# ALARM_POWER.net
KiCad netlist of a schematic drawn in Altium Designer
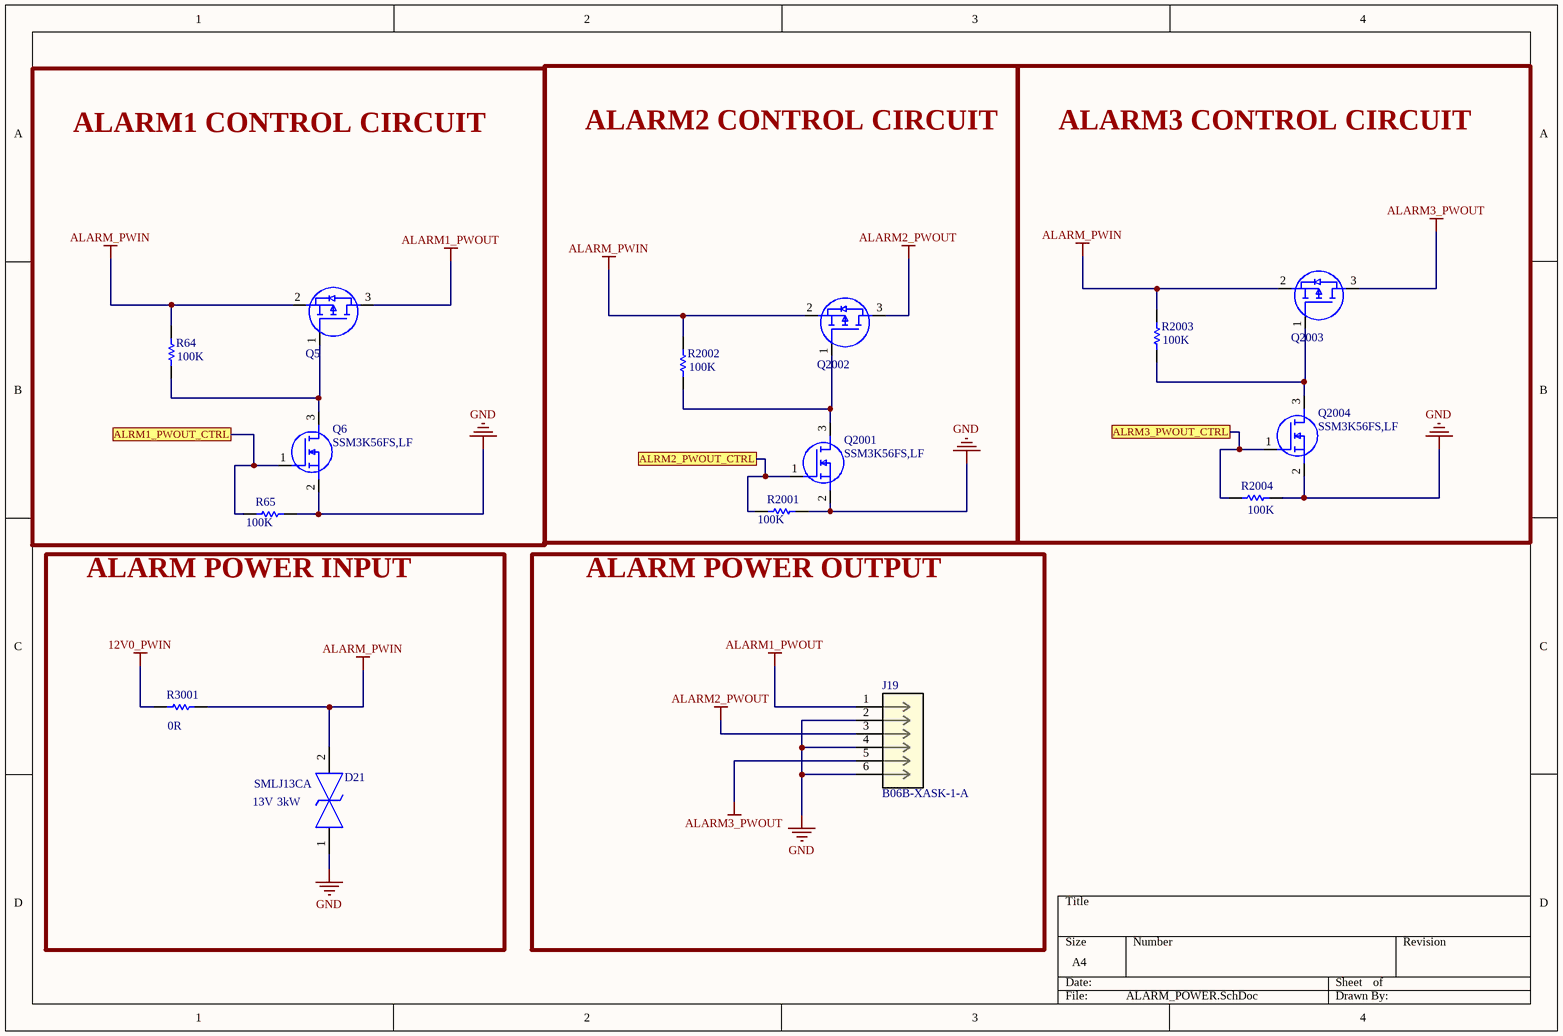
[diagram p0: ALARM_POWER.SchDoc]

(export (version "E")
  (design (tool "Eeschema 10.0.6"))
  (components
    (comp (ref "D21")
      (value "SMLJ13CA")
      (footprint "MareLux24Lib:DO-214AB, SMC")
      (description "21.5V Clamp 139.4A Ipp Tvs Diode Surface Mount SMC (DO-214AB)")
      (fields
        (field (name "ALTIUM_VALUE") "3kW")
        (field (name "TOLERANCE") "UD")
        (field (name "VOLTAGE") "13V")
      )
      (libsource (lib "MareLux24Lib") (part "SMLJ13CA"))
    )
    (comp (ref "J19")
      (value "B06B-XASK-1-A")
      (footprint "conn6_2132415-6_TEC")
      (description "No Description Available")
      (libsource (lib "2132415-6") (part "2132415-6"))
    )
    (comp (ref "Q5")
      (value "SQM110P06-8M9L_GE3")
      (footprint "SQM110P06_MOSFET")
      (description "P-Channel 60 V 110A (Tc) 230W (Tc) Surface Mount TO-263 (D2PAK)")
      (fields (field (name "VOLTAGE") "20 V") (field (name "POWER") "110A"))
      (libsource (lib "MareLux24Lib") (part "SQM110P06-8M9L_GE3"))
    )
    (comp (ref "Q6")
      (value "SSM3K56FS,LF")
      (footprint "SSM3K56FS,LF:SSM_TOS")
      (description "MOSFET (N-Channel)")
      (fields (field (name "MOUSER PART NUMBER") "757-SSM3K56FSLF"))
      (libsource (lib "*") (part "SSM3K56FS,LF"))
    )
    (comp (ref "Q2001")
      (value "SSM3K56FS,LF")
      (footprint "SSM3K56FS,LF:SSM_TOS")
      (description "MOSFET (N-Channel)")
      (fields (field (name "MOUSER PART NUMBER") "757-SSM3K56FSLF"))
      (libsource (lib "*") (part "SSM3K56FS,LF"))
    )
    (comp (ref "Q2002")
      (value "SQM110P06-8M9L_GE3")
      (footprint "SQM110P06_MOSFET")
      (description "P-Channel 60 V 110A (Tc) 230W (Tc) Surface Mount TO-263 (D2PAK)")
      (fields (field (name "VOLTAGE") "20 V") (field (name "POWER") "110A"))
      (libsource (lib "MareLux24Lib") (part "SQM110P06-8M9L_GE3"))
    )
    (comp (ref "Q2003")
      (value "SQM110P06-8M9L_GE3")
      (footprint "SQM110P06_MOSFET")
      (description "P-Channel 60 V 110A (Tc) 230W (Tc) Surface Mount TO-263 (D2PAK)")
      (fields (field (name "VOLTAGE") "20 V") (field (name "POWER") "110A"))
      (libsource (lib "MareLux24Lib") (part "SQM110P06-8M9L_GE3"))
    )
    (comp (ref "Q2004")
      (value "SSM3K56FS,LF")
      (footprint "SSM3K56FS,LF:SSM_TOS")
      (description "MOSFET (N-Channel)")
      (fields (field (name "MOUSER PART NUMBER") "757-SSM3K56FSLF"))
      (libsource (lib "*") (part "SSM3K56FS,LF"))
    )
    (comp (ref "R64")
      (value "100K")
      (footprint "RES_0402_SMD")
      (description "Generic Chip Res")
      (fields (field (name "PART NUMBER") "RMCF0402JT100K"))
      (libsource (lib "MareLux24Lib") (part "RES_GEN_SMD"))
    )
    (comp (ref "R65")
      (value "100K")
      (footprint "RES_0402_SMD")
      (description "Generic Chip Res")
      (fields (field (name "PART NUMBER") "RMCF0402JT100K"))
      (libsource (lib "MareLux24Lib") (part "RES_GEN_SMD"))
    )
    (comp (ref "R2001")
      (value "100K")
      (footprint "RES_0402_SMD")
      (description "Generic Chip Res")
      (fields (field (name "PART NUMBER") "RMCF0402JT100K"))
      (libsource (lib "MareLux24Lib") (part "RES_GEN_SMD"))
    )
    (comp (ref "R2002")
      (value "100K")
      (footprint "RES_0402_SMD")
      (description "Generic Chip Res")
      (fields (field (name "PART NUMBER") "RMCF0402JT100K"))
      (libsource (lib "MareLux24Lib") (part "RES_GEN_SMD"))
    )
    (comp (ref "R2003")
      (value "100K")
      (footprint "RES_0402_SMD")
      (description "Generic Chip Res")
      (fields (field (name "PART NUMBER") "RMCF0402JT100K"))
      (libsource (lib "MareLux24Lib") (part "RES_GEN_SMD"))
    )
    (comp (ref "R2004")
      (value "100K")
      (footprint "RES_0402_SMD")
      (description "Generic Chip Res")
      (fields (field (name "PART NUMBER") "RMCF0402JT100K"))
      (libsource (lib "MareLux24Lib") (part "RES_GEN_SMD"))
    )
    (comp (ref "R3001")
      (value "0R")
      (footprint "MareLux24Lib:RES_1206_SMD")
      (description "Generic Chip Res")
      (libsource (lib "MareLux24Lib") (part "RES_GEN_SMD"))
    )
  )
  (nets
    (net (code "1") (name "/ALRM1_PWOUT_CTRL") (class "Default")
      (node (ref "Q6") (pin "1") (pinfunction "G_1") (pintype "passive"))
      (node (ref "R65") (pin "2") (pinfunction "2_2") (pintype "passive"))
    )
    (net (code "2") (name "/ALRM2_PWOUT_CTRL") (class "Default")
      (node (ref "Q2001") (pin "1") (pinfunction "G_1") (pintype "passive"))
      (node (ref "R2001") (pin "2") (pinfunction "2_2") (pintype "passive"))
    )
    (net (code "3") (name "/ALRM3_PWOUT_CTRL") (class "Default")
      (node (ref "Q2004") (pin "1") (pinfunction "G_1") (pintype "passive"))
      (node (ref "R2004") (pin "2") (pinfunction "2_2") (pintype "passive"))
    )
    (net (code "4") (name "12V0_PWIN") (class "Default")
      (node (ref "R3001") (pin "1") (pinfunction "1_1") (pintype "passive"))
    )
    (net (code "5") (name "ALARM1_PWOUT") (class "Default")
      (node (ref "J19") (pin "1") (pinfunction "1_1") (pintype "passive"))
      (node (ref "Q5") (pin "3") (pinfunction "D_3") (pintype "passive"))
    )
    (net (code "6") (name "ALARM2_PWOUT") (class "Default")
      (node (ref "J19") (pin "3") (pinfunction "3_3") (pintype "passive"))
      (node (ref "Q2002") (pin "3") (pinfunction "D_3") (pintype "passive"))
    )
    (net (code "7") (name "ALARM3_PWOUT") (class "Default")
      (node (ref "J19") (pin "5") (pinfunction "5_5") (pintype "passive"))
      (node (ref "Q2003") (pin "3") (pinfunction "D_3") (pintype "passive"))
    )
    (net (code "8") (name "ALARM_PWIN") (class "Default")
      (node (ref "D21") (pin "2") (pinfunction "2_2") (pintype "passive"))
      (node (ref "Q2002") (pin "2") (pinfunction "S_2") (pintype "passive"))
      (node (ref "Q2003") (pin "2") (pinfunction "S_2") (pintype "passive"))
      (node (ref "Q5") (pin "2") (pinfunction "S_2") (pintype "passive"))
      (node (ref "R2002") (pin "2") (pinfunction "2_2") (pintype "passive"))
      (node (ref "R2003") (pin "2") (pinfunction "2_2") (pintype "passive"))
      (node (ref "R3001") (pin "2") (pinfunction "2_2") (pintype "passive"))
      (node (ref "R64") (pin "2") (pinfunction "2_2") (pintype "passive"))
    )
    (net (code "9") (name "GND") (class "Default")
      (node (ref "D21") (pin "1") (pinfunction "1_1") (pintype "passive"))
      (node (ref "J19") (pin "2") (pinfunction "2_2") (pintype "passive"))
      (node (ref "J19") (pin "4") (pinfunction "4_4") (pintype "passive"))
      (node (ref "J19") (pin "6") (pinfunction "6_6") (pintype "passive"))
      (node (ref "Q2001") (pin "2") (pinfunction "S_2") (pintype "passive"))
      (node (ref "Q2004") (pin "2") (pinfunction "S_2") (pintype "passive"))
      (node (ref "Q6") (pin "2") (pinfunction "S_2") (pintype "passive"))
      (node (ref "R2001") (pin "1") (pinfunction "1_1") (pintype "passive"))
      (node (ref "R2004") (pin "1") (pinfunction "1_1") (pintype "passive"))
      (node (ref "R65") (pin "1") (pinfunction "1_1") (pintype "passive"))
    )
    (net (code "10") (name "Net-(Q5-G)") (class "Default")
      (node (ref "Q5") (pin "1") (pinfunction "G_1") (pintype "passive"))
      (node (ref "Q6") (pin "3") (pinfunction "D_3") (pintype "passive"))
      (node (ref "R64") (pin "1") (pinfunction "1_1") (pintype "passive"))
    )
    (net (code "11") (name "Net-(Q2001-D)") (class "Default")
      (node (ref "Q2001") (pin "3") (pinfunction "D_3") (pintype "passive"))
      (node (ref "Q2002") (pin "1") (pinfunction "G_1") (pintype "passive"))
      (node (ref "R2002") (pin "1") (pinfunction "1_1") (pintype "passive"))
    )
    (net (code "12") (name "Net-(Q2003-G)") (class "Default")
      (node (ref "Q2003") (pin "1") (pinfunction "G_1") (pintype "passive"))
      (node (ref "Q2004") (pin "3") (pinfunction "D_3") (pintype "passive"))
      (node (ref "R2003") (pin "1") (pinfunction "1_1") (pintype "passive"))
    )
  )
)
